# Interconnect_board_limit_switches_v1p7.net
KiCad netlist of a schematic drawn in EAGLE
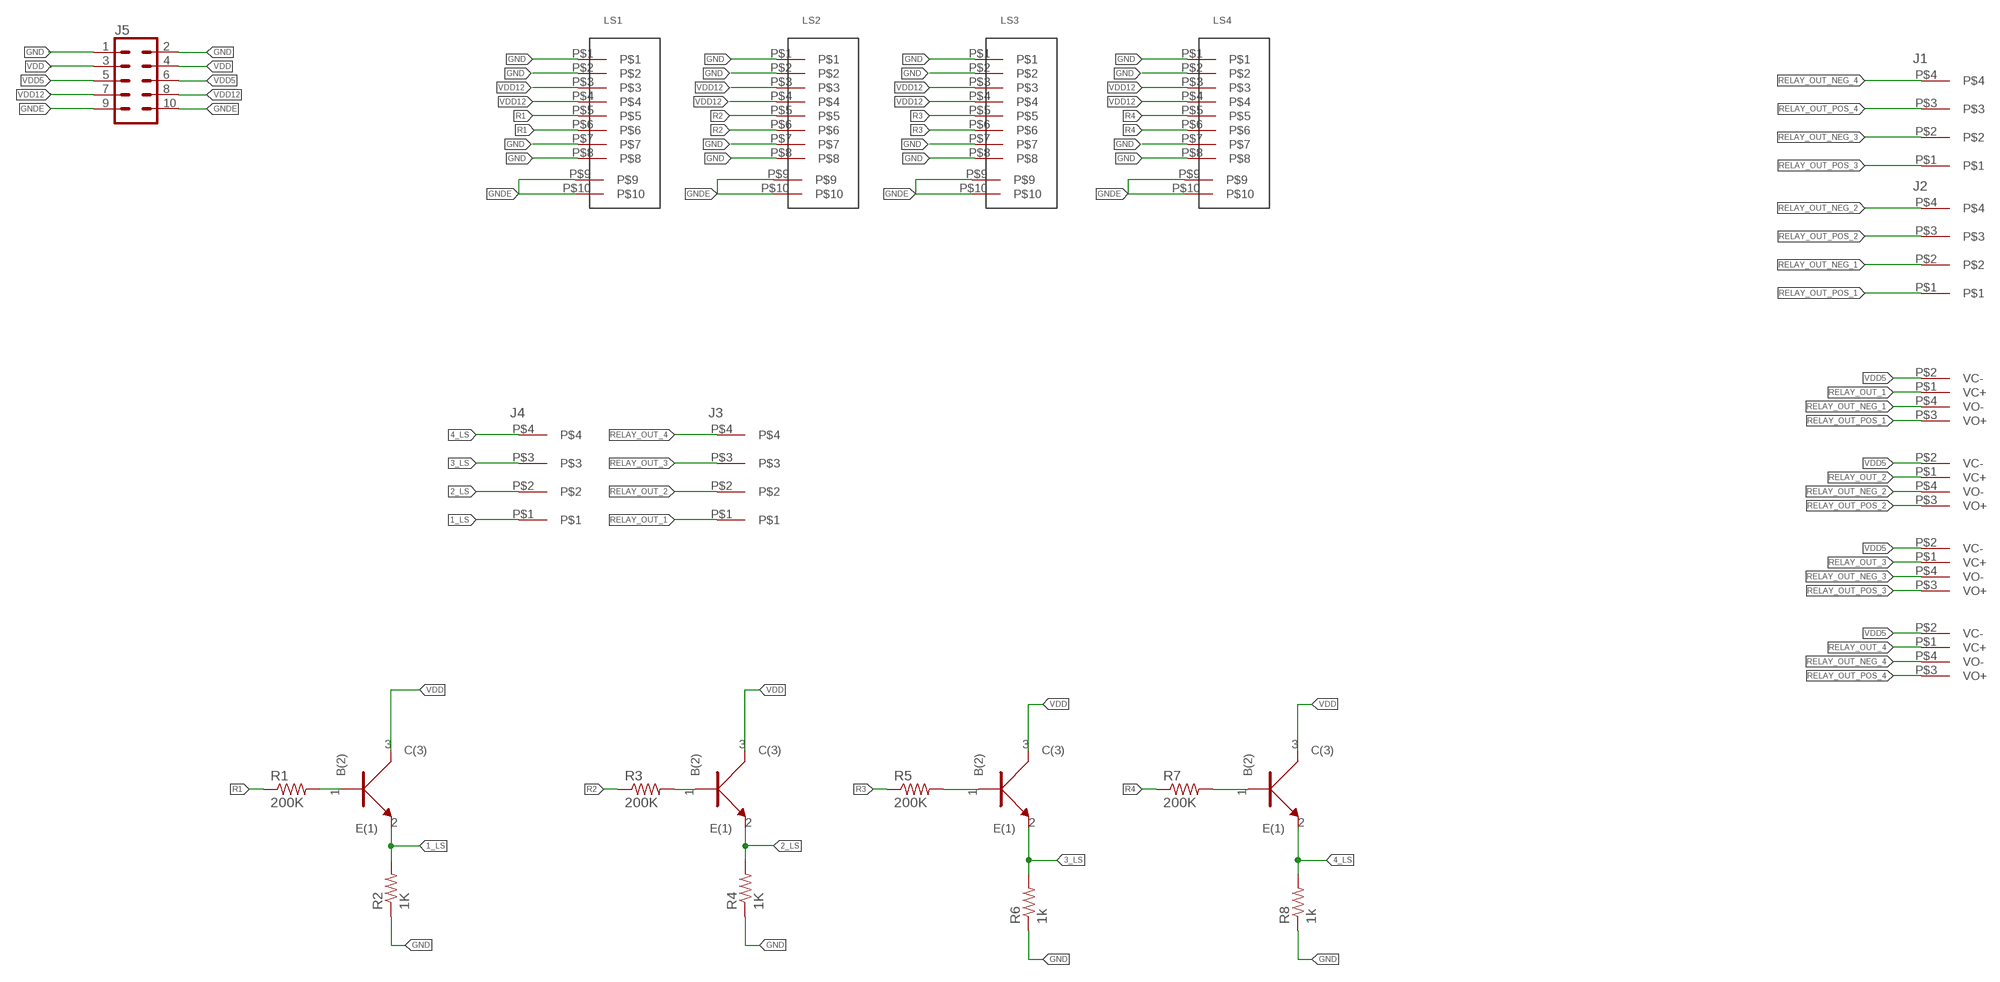
[diagram p0: schematic, sheet 1]

(export (version "E")
  (design (tool "Eeschema 10.0.6"))
  (components
    (comp (ref "J1")
      (value "3.81MM_1_X_4_RT_ANGLE_PLUG_HEADER")
      (footprint "eagle-import:1X4_3.81MM_PITCH")
      (libsource (lib "eagle-import") (part "3.81MM_1_X_4_RT_ANGLE_PLUG_HEADER"))
    )
    (comp (ref "J2")
      (value "3.81MM_1_X_4_RT_ANGLE_PLUG_HEADER")
      (footprint "eagle-import:1X4_3.81MM_PITCH")
      (libsource (lib "eagle-import") (part "3.81MM_1_X_4_RT_ANGLE_PLUG_HEADER"))
    )
    (comp (ref "J3")
      (value "3.81MM_1_X_4_RT_ANGLE_PLUG_HEADER")
      (footprint "eagle-import:1X4_3.81MM_PITCH")
      (libsource (lib "eagle-import") (part "3.81MM_1_X_4_RT_ANGLE_PLUG_HEADER"))
    )
    (comp (ref "J4")
      (value "3.81MM_1_X_4_RT_ANGLE_PLUG_HEADER")
      (footprint "eagle-import:1X4_3.81MM_PITCH")
      (libsource (lib "eagle-import") (part "3.81MM_1_X_4_RT_ANGLE_PLUG_HEADER"))
    )
    (comp (ref "J5")
      (value "CONN_05X2PTH")
      (footprint "eagle-import:2X5")
      (libsource (lib "eagle-import") (part "CONN_05X2PTH"))
    )
    (comp (ref "LS1")
      (value "RJ45_SMTRJ")
      (footprint "eagle-import:RJ45_SMT")
      (libsource (lib "eagle-import") (part "RJ45_SMTRJ"))
    )
    (comp (ref "LS2")
      (value "RJ45_SMTRJ")
      (footprint "eagle-import:RJ45_SMT")
      (libsource (lib "eagle-import") (part "RJ45_SMTRJ"))
    )
    (comp (ref "LS3")
      (value "RJ45_SMTRJ")
      (footprint "eagle-import:RJ45_SMT")
      (libsource (lib "eagle-import") (part "RJ45_SMTRJ"))
    )
    (comp (ref "LS4")
      (value "RJ45_SMTRJ")
      (footprint "eagle-import:RJ45_SMT")
      (libsource (lib "eagle-import") (part "RJ45_SMTRJ"))
    )
    (comp (ref "R1")
      (value "200K")
      (footprint "eagle-import:0402")
      (libsource (lib "eagle-import") (part "R_0402"))
    )
    (comp (ref "R2")
      (value "1K")
      (footprint "eagle-import:0402")
      (libsource (lib "eagle-import") (part "R_0402"))
    )
    (comp (ref "R3")
      (value "200K")
      (footprint "eagle-import:0402")
      (libsource (lib "eagle-import") (part "R_0402"))
    )
    (comp (ref "R4")
      (value "1K")
      (footprint "eagle-import:0402")
      (libsource (lib "eagle-import") (part "R_0402"))
    )
    (comp (ref "R5")
      (value "200K")
      (footprint "eagle-import:0402")
      (libsource (lib "eagle-import") (part "R_0402"))
    )
    (comp (ref "R6")
      (value "1k")
      (footprint "eagle-import:0402")
      (libsource (lib "eagle-import") (part "R_0402"))
    )
    (comp (ref "R7")
      (value "200K")
      (footprint "eagle-import:0402")
      (libsource (lib "eagle-import") (part "R_0402"))
    )
    (comp (ref "R8")
      (value "1k")
      (footprint "eagle-import:0402")
      (libsource (lib "eagle-import") (part "R_0402"))
    )
    (comp (ref "RELAY_1")
      (value "RELAY_KYOTO_KF0604D")
      (footprint "eagle-import:RELAY_KYOTO_KF0604D")
      (libsource (lib "eagle-import") (part "RELAY_KYOTO_KF0604D"))
    )
    (comp (ref "RELAY_2")
      (value "RELAY_KYOTO_KF0604D")
      (footprint "eagle-import:RELAY_KYOTO_KF0604D")
      (libsource (lib "eagle-import") (part "RELAY_KYOTO_KF0604D"))
    )
    (comp (ref "RELAY_4")
      (value "RELAY_KYOTO_KF0604D")
      (footprint "eagle-import:RELAY_KYOTO_KF0604D")
      (libsource (lib "eagle-import") (part "RELAY_KYOTO_KF0604D"))
    )
    (comp (ref "RELAY_5")
      (value "RELAY_KYOTO_KF0604D")
      (footprint "eagle-import:RELAY_KYOTO_KF0604D")
      (libsource (lib "eagle-import") (part "RELAY_KYOTO_KF0604D"))
    )
    (comp (ref "U1")
      (value "BC846BW")
      (footprint "eagle-import:SOT323")
      (libsource (lib "eagle-import") (part "BC846BW"))
    )
    (comp (ref "U2")
      (value "BC846BW")
      (footprint "eagle-import:SOT323")
      (libsource (lib "eagle-import") (part "BC846BW"))
    )
    (comp (ref "U3")
      (value "BC846BW")
      (footprint "eagle-import:SOT323")
      (libsource (lib "eagle-import") (part "BC846BW"))
    )
    (comp (ref "U4")
      (value "BC846BW")
      (footprint "eagle-import:SOT323")
      (libsource (lib "eagle-import") (part "BC846BW"))
    )
  )
  (nets
    (net (code "1") (name "1_LS") (class "Default")
      (node (ref "J4") (pin "P$1") (pinfunction "P$1_P$1") (pintype "bidirectional"))
      (node (ref "R2") (pin "P$2") (pinfunction "2_P$2") (pintype "passive"))
      (node (ref "U1") (pin "2") (pinfunction "E(1)_2") (pintype "output"))
    )
    (net (code "2") (name "2_LS") (class "Default")
      (node (ref "J4") (pin "P$2") (pinfunction "P$2_P$2") (pintype "bidirectional"))
      (node (ref "R4") (pin "P$2") (pinfunction "2_P$2") (pintype "passive"))
      (node (ref "U2") (pin "2") (pinfunction "E(1)_2") (pintype "output"))
    )
    (net (code "3") (name "3_LS") (class "Default")
      (node (ref "J4") (pin "P$3") (pinfunction "P$3_P$3") (pintype "bidirectional"))
      (node (ref "R6") (pin "P$2") (pinfunction "2_P$2") (pintype "passive"))
      (node (ref "U3") (pin "2") (pinfunction "E(1)_2") (pintype "output"))
    )
    (net (code "4") (name "4_LS") (class "Default")
      (node (ref "J4") (pin "P$4") (pinfunction "P$4_P$4") (pintype "bidirectional"))
      (node (ref "R8") (pin "P$2") (pinfunction "2_P$2") (pintype "passive"))
      (node (ref "U4") (pin "2") (pinfunction "E(1)_2") (pintype "output"))
    )
    (net (code "5") (name "GND") (class "Default")
      (node (ref "J5") (pin "1") (pinfunction "1_1") (pintype "passive"))
      (node (ref "J5") (pin "2") (pinfunction "2_2") (pintype "passive"))
      (node (ref "LS1") (pin "P$1") (pinfunction "P$1_P$1") (pintype "bidirectional"))
      (node (ref "LS1") (pin "P$2") (pinfunction "P$2_P$2") (pintype "bidirectional"))
      (node (ref "LS1") (pin "P$7") (pinfunction "P$7_P$7") (pintype "bidirectional"))
      (node (ref "LS1") (pin "P$8") (pinfunction "P$8_P$8") (pintype "bidirectional"))
      (node (ref "LS2") (pin "P$1") (pinfunction "P$1_P$1") (pintype "bidirectional"))
      (node (ref "LS2") (pin "P$2") (pinfunction "P$2_P$2") (pintype "bidirectional"))
      (node (ref "LS2") (pin "P$7") (pinfunction "P$7_P$7") (pintype "bidirectional"))
      (node (ref "LS2") (pin "P$8") (pinfunction "P$8_P$8") (pintype "bidirectional"))
      (node (ref "LS3") (pin "P$1") (pinfunction "P$1_P$1") (pintype "bidirectional"))
      (node (ref "LS3") (pin "P$2") (pinfunction "P$2_P$2") (pintype "bidirectional"))
      (node (ref "LS3") (pin "P$7") (pinfunction "P$7_P$7") (pintype "bidirectional"))
      (node (ref "LS3") (pin "P$8") (pinfunction "P$8_P$8") (pintype "bidirectional"))
      (node (ref "LS4") (pin "P$1") (pinfunction "P$1_P$1") (pintype "bidirectional"))
      (node (ref "LS4") (pin "P$2") (pinfunction "P$2_P$2") (pintype "bidirectional"))
      (node (ref "LS4") (pin "P$7") (pinfunction "P$7_P$7") (pintype "bidirectional"))
      (node (ref "LS4") (pin "P$8") (pinfunction "P$8_P$8") (pintype "bidirectional"))
      (node (ref "R2") (pin "P$1") (pinfunction "1_P$1") (pintype "passive"))
      (node (ref "R4") (pin "P$1") (pinfunction "1_P$1") (pintype "passive"))
      (node (ref "R6") (pin "P$1") (pinfunction "1_P$1") (pintype "passive"))
      (node (ref "R8") (pin "P$1") (pinfunction "1_P$1") (pintype "passive"))
    )
    (net (code "6") (name "GNDE") (class "Default")
      (node (ref "J5") (pin "10") (pinfunction "10_10") (pintype "passive"))
      (node (ref "J5") (pin "9") (pinfunction "9_9") (pintype "passive"))
      (node (ref "LS1") (pin "P$10") (pinfunction "P$10_P$10") (pintype "bidirectional"))
      (node (ref "LS1") (pin "P$9") (pinfunction "P$9_P$9") (pintype "bidirectional"))
      (node (ref "LS2") (pin "P$10") (pinfunction "P$10_P$10") (pintype "bidirectional"))
      (node (ref "LS2") (pin "P$9") (pinfunction "P$9_P$9") (pintype "bidirectional"))
      (node (ref "LS3") (pin "P$10") (pinfunction "P$10_P$10") (pintype "bidirectional"))
      (node (ref "LS3") (pin "P$9") (pinfunction "P$9_P$9") (pintype "bidirectional"))
      (node (ref "LS4") (pin "P$10") (pinfunction "P$10_P$10") (pintype "bidirectional"))
      (node (ref "LS4") (pin "P$9") (pinfunction "P$9_P$9") (pintype "bidirectional"))
    )
    (net (code "7") (name "Net-(R1-2)") (class "Default")
      (node (ref "R1") (pin "P$2") (pinfunction "2_P$2") (pintype "passive"))
      (node (ref "U1") (pin "1") (pinfunction "B(2)_1") (pintype "input"))
    )
    (net (code "8") (name "Net-(R3-2)") (class "Default")
      (node (ref "R3") (pin "P$2") (pinfunction "2_P$2") (pintype "passive"))
      (node (ref "U2") (pin "1") (pinfunction "B(2)_1") (pintype "input"))
    )
    (net (code "9") (name "Net-(R5-2)") (class "Default")
      (node (ref "R5") (pin "P$2") (pinfunction "2_P$2") (pintype "passive"))
      (node (ref "U3") (pin "1") (pinfunction "B(2)_1") (pintype "input"))
    )
    (net (code "10") (name "Net-(R7-2)") (class "Default")
      (node (ref "R7") (pin "P$2") (pinfunction "2_P$2") (pintype "passive"))
      (node (ref "U4") (pin "1") (pinfunction "B(2)_1") (pintype "input"))
    )
    (net (code "11") (name "R1") (class "Default")
      (node (ref "LS1") (pin "P$5") (pinfunction "P$5_P$5") (pintype "bidirectional"))
      (node (ref "LS1") (pin "P$6") (pinfunction "P$6_P$6") (pintype "bidirectional"))
      (node (ref "R1") (pin "P$1") (pinfunction "1_P$1") (pintype "passive"))
    )
    (net (code "12") (name "R2") (class "Default")
      (node (ref "LS2") (pin "P$5") (pinfunction "P$5_P$5") (pintype "bidirectional"))
      (node (ref "LS2") (pin "P$6") (pinfunction "P$6_P$6") (pintype "bidirectional"))
      (node (ref "R3") (pin "P$1") (pinfunction "1_P$1") (pintype "passive"))
    )
    (net (code "13") (name "R3") (class "Default")
      (node (ref "LS3") (pin "P$5") (pinfunction "P$5_P$5") (pintype "bidirectional"))
      (node (ref "LS3") (pin "P$6") (pinfunction "P$6_P$6") (pintype "bidirectional"))
      (node (ref "R5") (pin "P$1") (pinfunction "1_P$1") (pintype "passive"))
    )
    (net (code "14") (name "R4") (class "Default")
      (node (ref "LS4") (pin "P$5") (pinfunction "P$5_P$5") (pintype "bidirectional"))
      (node (ref "LS4") (pin "P$6") (pinfunction "P$6_P$6") (pintype "bidirectional"))
      (node (ref "R7") (pin "P$1") (pinfunction "1_P$1") (pintype "passive"))
    )
    (net (code "15") (name "RELAY_OUT_1") (class "Default")
      (node (ref "J3") (pin "P$1") (pinfunction "P$1_P$1") (pintype "bidirectional"))
      (node (ref "RELAY_1") (pin "P$1") (pinfunction "VC+_P$1") (pintype "bidirectional"))
    )
    (net (code "16") (name "RELAY_OUT_2") (class "Default")
      (node (ref "J3") (pin "P$2") (pinfunction "P$2_P$2") (pintype "bidirectional"))
      (node (ref "RELAY_2") (pin "P$1") (pinfunction "VC+_P$1") (pintype "bidirectional"))
    )
    (net (code "17") (name "RELAY_OUT_3") (class "Default")
      (node (ref "J3") (pin "P$3") (pinfunction "P$3_P$3") (pintype "bidirectional"))
      (node (ref "RELAY_5") (pin "P$1") (pinfunction "VC+_P$1") (pintype "bidirectional"))
    )
    (net (code "18") (name "RELAY_OUT_4") (class "Default")
      (node (ref "J3") (pin "P$4") (pinfunction "P$4_P$4") (pintype "bidirectional"))
      (node (ref "RELAY_4") (pin "P$1") (pinfunction "VC+_P$1") (pintype "bidirectional"))
    )
    (net (code "19") (name "RELAY_OUT_NEG_1") (class "Default")
      (node (ref "J2") (pin "P$2") (pinfunction "P$2_P$2") (pintype "bidirectional"))
      (node (ref "RELAY_1") (pin "P$4") (pinfunction "VO-_P$4") (pintype "bidirectional"))
    )
    (net (code "20") (name "RELAY_OUT_NEG_2") (class "Default")
      (node (ref "J2") (pin "P$4") (pinfunction "P$4_P$4") (pintype "bidirectional"))
      (node (ref "RELAY_2") (pin "P$4") (pinfunction "VO-_P$4") (pintype "bidirectional"))
    )
    (net (code "21") (name "RELAY_OUT_NEG_3") (class "Default")
      (node (ref "J1") (pin "P$2") (pinfunction "P$2_P$2") (pintype "bidirectional"))
      (node (ref "RELAY_5") (pin "P$4") (pinfunction "VO-_P$4") (pintype "bidirectional"))
    )
    (net (code "22") (name "RELAY_OUT_NEG_4") (class "Default")
      (node (ref "J1") (pin "P$4") (pinfunction "P$4_P$4") (pintype "bidirectional"))
      (node (ref "RELAY_4") (pin "P$4") (pinfunction "VO-_P$4") (pintype "bidirectional"))
    )
    (net (code "23") (name "RELAY_OUT_POS_1") (class "Default")
      (node (ref "J2") (pin "P$1") (pinfunction "P$1_P$1") (pintype "bidirectional"))
      (node (ref "RELAY_1") (pin "P$3") (pinfunction "VO+_P$3") (pintype "bidirectional"))
    )
    (net (code "24") (name "RELAY_OUT_POS_2") (class "Default")
      (node (ref "J2") (pin "P$3") (pinfunction "P$3_P$3") (pintype "bidirectional"))
      (node (ref "RELAY_2") (pin "P$3") (pinfunction "VO+_P$3") (pintype "bidirectional"))
    )
    (net (code "25") (name "RELAY_OUT_POS_3") (class "Default")
      (node (ref "J1") (pin "P$1") (pinfunction "P$1_P$1") (pintype "bidirectional"))
      (node (ref "RELAY_5") (pin "P$3") (pinfunction "VO+_P$3") (pintype "bidirectional"))
    )
    (net (code "26") (name "RELAY_OUT_POS_4") (class "Default")
      (node (ref "J1") (pin "P$3") (pinfunction "P$3_P$3") (pintype "bidirectional"))
      (node (ref "RELAY_4") (pin "P$3") (pinfunction "VO+_P$3") (pintype "bidirectional"))
    )
    (net (code "27") (name "VDD") (class "Default")
      (node (ref "J5") (pin "3") (pinfunction "3_3") (pintype "passive"))
      (node (ref "J5") (pin "4") (pinfunction "4_4") (pintype "passive"))
      (node (ref "U1") (pin "3") (pinfunction "C(3)_3") (pintype "input"))
      (node (ref "U2") (pin "3") (pinfunction "C(3)_3") (pintype "input"))
      (node (ref "U3") (pin "3") (pinfunction "C(3)_3") (pintype "input"))
      (node (ref "U4") (pin "3") (pinfunction "C(3)_3") (pintype "input"))
    )
    (net (code "28") (name "VDD5") (class "Default")
      (node (ref "J5") (pin "5") (pinfunction "5_5") (pintype "passive"))
      (node (ref "J5") (pin "6") (pinfunction "6_6") (pintype "passive"))
      (node (ref "RELAY_1") (pin "P$2") (pinfunction "VC-_P$2") (pintype "bidirectional"))
      (node (ref "RELAY_2") (pin "P$2") (pinfunction "VC-_P$2") (pintype "bidirectional"))
      (node (ref "RELAY_4") (pin "P$2") (pinfunction "VC-_P$2") (pintype "bidirectional"))
      (node (ref "RELAY_5") (pin "P$2") (pinfunction "VC-_P$2") (pintype "bidirectional"))
    )
    (net (code "29") (name "VDD12") (class "Default")
      (node (ref "J5") (pin "7") (pinfunction "7_7") (pintype "passive"))
      (node (ref "J5") (pin "8") (pinfunction "8_8") (pintype "passive"))
      (node (ref "LS1") (pin "P$3") (pinfunction "P$3_P$3") (pintype "bidirectional"))
      (node (ref "LS1") (pin "P$4") (pinfunction "P$4_P$4") (pintype "bidirectional"))
      (node (ref "LS2") (pin "P$3") (pinfunction "P$3_P$3") (pintype "bidirectional"))
      (node (ref "LS2") (pin "P$4") (pinfunction "P$4_P$4") (pintype "bidirectional"))
      (node (ref "LS3") (pin "P$3") (pinfunction "P$3_P$3") (pintype "bidirectional"))
      (node (ref "LS3") (pin "P$4") (pinfunction "P$4_P$4") (pintype "bidirectional"))
      (node (ref "LS4") (pin "P$3") (pinfunction "P$3_P$3") (pintype "bidirectional"))
      (node (ref "LS4") (pin "P$4") (pinfunction "P$4_P$4") (pintype "bidirectional"))
    )
  )
)
